# Gpio_RTC.net
KiCad netlist of a schematic drawn in Altium Designer
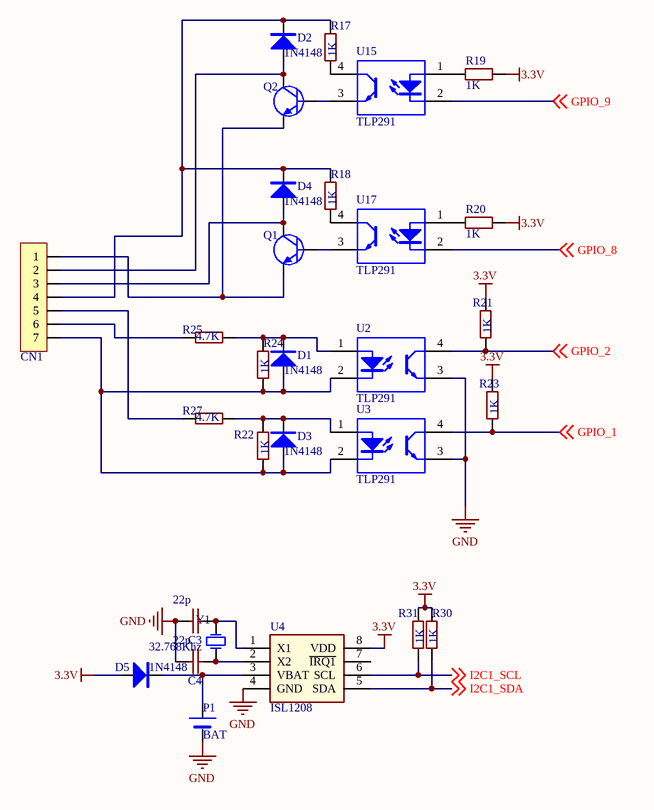
[diagram p0: Gpio_RTC.SchDoc]

(export (version "E")
  (design (tool "Eeschema 10.0.6"))
  (components
    (comp (ref "C3")
      (value "22p")
      (footprint "0805SMD_Cap")
      (description "贴片电容")
      (libsource (lib "ST_GND_Sch") (part "SMD_Cap"))
    )
    (comp (ref "C4")
      (value "22p")
      (footprint "0805SMD_Cap")
      (description "贴片电容")
      (libsource (lib "ST_GND_Sch") (part "SMD_Cap"))
    )
    (comp (ref "CN1")
      (value "CON7")
      (footprint "WJ15EDGRM-3.81-7P")
      (description "连接器")
      (libsource (lib "ST_GND_Sch") (part "CON7"))
    )
    (comp (ref "D1")
      (value "1N4148")
      (footprint "二极管SOD-123")
      (description "二极管")
      (libsource (lib "ST_GND_Sch") (part "DIODE"))
    )
    (comp (ref "D2")
      (value "1N4148")
      (footprint "二极管SOD-123")
      (description "二极管")
      (libsource (lib "ST_GND_Sch") (part "DIODE"))
    )
    (comp (ref "D3")
      (value "1N4148")
      (footprint "二极管SOD-123")
      (description "二极管")
      (libsource (lib "ST_GND_Sch") (part "DIODE"))
    )
    (comp (ref "D4")
      (value "1N4148")
      (footprint "二极管SOD-123")
      (description "二极管")
      (libsource (lib "ST_GND_Sch") (part "DIODE"))
    )
    (comp (ref "D5")
      (value "1N4148")
      (footprint "二极管SOD-123")
      (description "二极管")
      (libsource (lib "ST_GND_Sch") (part "DIODE"))
    )
    (comp (ref "P1") (value "BAT") (footprint "CR1220") (libsource (lib "ST_GND_Sch") (part "BAT")))
    (comp (ref "Q1")
      (value "1318")
      (footprint "SOT-23")
      (description "三极管")
      (fields (field (name "PUBLISHER") "Altium Limited"))
      (libsource (lib "ST_GND_Sch") (part "三极管"))
    )
    (comp (ref "Q2")
      (value "1318")
      (footprint "SOT-23")
      (description "三极管")
      (fields (field (name "PUBLISHER") "Altium Limited"))
      (libsource (lib "ST_GND_Sch") (part "三极管"))
    )
    (comp (ref "R17")
      (value "1K")
      (footprint "0805_SMD_R")
      (description "贴片电阻")
      (libsource (lib "ST_GND_Sch") (part "SMD_0805"))
    )
    (comp (ref "R18")
      (value "1K")
      (footprint "0805_SMD_R")
      (description "贴片电阻")
      (libsource (lib "ST_GND_Sch") (part "SMD_0805"))
    )
    (comp (ref "R19")
      (value "1K")
      (footprint "0805_SMD_R")
      (description "贴片电阻")
      (libsource (lib "") (part "SMD_0805_2"))
    )
    (comp (ref "R20")
      (value "1K")
      (footprint "0805_SMD_R")
      (description "贴片电阻")
      (libsource (lib "") (part "SMD_0805_2"))
    )
    (comp (ref "R21")
      (value "1K")
      (footprint "0805_SMD_R")
      (description "贴片电阻")
      (libsource (lib "ST_GND_Sch") (part "SMD_0805"))
    )
    (comp (ref "R22")
      (value "1K")
      (footprint "0805_SMD_R")
      (description "贴片电阻")
      (libsource (lib "ST_GND_Sch") (part "SMD_0805"))
    )
    (comp (ref "R23")
      (value "1K")
      (footprint "0805_SMD_R")
      (description "贴片电阻")
      (libsource (lib "ST_GND_Sch") (part "SMD_0805"))
    )
    (comp (ref "R24")
      (value "1K")
      (footprint "0805_SMD_R")
      (description "贴片电阻")
      (libsource (lib "ST_GND_Sch") (part "SMD_0805"))
    )
    (comp (ref "R25")
      (value "4.7K")
      (footprint "0805_SMD_R")
      (description "贴片电阻")
      (libsource (lib "") (part "SMD_0805_1"))
    )
    (comp (ref "R27")
      (value "4.7K")
      (footprint "0805_SMD_R")
      (description "贴片电阻")
      (libsource (lib "") (part "SMD_0805_1"))
    )
    (comp (ref "R30")
      (value "1K")
      (footprint "0805_SMD_R")
      (description "贴片电阻")
      (libsource (lib "") (part "SMD_0805_2"))
    )
    (comp (ref "R31")
      (value "1K")
      (footprint "0805_SMD_R")
      (description "贴片电阻")
      (libsource (lib "") (part "SMD_0805_2"))
    )
    (comp (ref "U2") (value "TLP291") (footprint "sop-4") (libsource (lib "ST_GND_Sch") (part "TLP291")))
    (comp (ref "U3") (value "TLP291") (footprint "sop-4") (libsource (lib "ST_GND_Sch") (part "TLP291")))
    (comp (ref "U4")
      (value "ISL1208")
      (footprint "运放SO8")
      (description "时钟芯片")
      (libsource (lib "ST_GND_Sch") (part "ISL1208"))
    )
    (comp (ref "U15") (value "TLP291") (footprint "sop-4") (libsource (lib "ST_GND_Sch") (part "TLP291")))
    (comp (ref "U17") (value "TLP291") (footprint "sop-4") (libsource (lib "ST_GND_Sch") (part "TLP291")))
    (comp (ref "Y1")
      (value "32.768Khz")
      (footprint "XTAL_0503_2Pin")
      (description "无源晶振贴装")
      (fields (field (name "PUBLISHER") "Altium Limited"))
      (libsource (lib "ST_GND_Sch") (part "XTAL"))
    )
  )
  (nets
    (net (code "1") (name "3.3V") (class "Default")
      (node (ref "D5") (pin "A") (pintype "passive"))
      (node (ref "R19") (pin "1") (pinfunction "1_1") (pintype "passive"))
      (node (ref "R20") (pin "1") (pinfunction "1_1") (pintype "passive"))
      (node (ref "R21") (pin "2") (pinfunction "2_2") (pintype "passive"))
      (node (ref "R23") (pin "2") (pinfunction "2_2") (pintype "passive"))
      (node (ref "R30") (pin "1") (pinfunction "1_1") (pintype "passive"))
      (node (ref "R31") (pin "1") (pinfunction "1_1") (pintype "passive"))
      (node (ref "U4") (pin "8") (pinfunction "VDD_8") (pintype "passive"))
    )
    (net (code "2") (name "GND") (class "Default")
      (node (ref "C3") (pin "1") (pintype "passive"))
      (node (ref "C4") (pin "1") (pintype "passive"))
      (node (ref "P1") (pin "2") (pinfunction "-_2") (pintype "passive"))
      (node (ref "U2") (pin "3") (pinfunction "3_3") (pintype "passive"))
      (node (ref "U3") (pin "3") (pinfunction "3_3") (pintype "passive"))
      (node (ref "U4") (pin "4") (pinfunction "GND_4") (pintype "passive"))
    )
    (net (code "3") (name "GPIO_1") (class "Default")
      (node (ref "R23") (pin "1") (pinfunction "1_1") (pintype "passive"))
      (node (ref "U3") (pin "4") (pinfunction "4_4") (pintype "passive"))
    )
    (net (code "4") (name "GPIO_2") (class "Default")
      (node (ref "R21") (pin "1") (pinfunction "1_1") (pintype "passive"))
      (node (ref "U2") (pin "4") (pinfunction "4_4") (pintype "passive"))
    )
    (net (code "5") (name "GPIO_8") (class "Default")
      (node (ref "U17") (pin "2") (pinfunction "2_2") (pintype "passive"))
    )
    (net (code "6") (name "GPIO_9") (class "Default")
      (node (ref "U15") (pin "2") (pinfunction "2_2") (pintype "passive"))
    )
    (net (code "7") (name "I2C1_SCL") (class "Default")
      (node (ref "R31") (pin "2") (pinfunction "2_2") (pintype "passive"))
      (node (ref "U4") (pin "6") (pinfunction "SCL_6") (pintype "passive"))
    )
    (net (code "8") (name "I2C1_SDA") (class "Default")
      (node (ref "R30") (pin "2") (pinfunction "2_2") (pintype "passive"))
      (node (ref "U4") (pin "5") (pinfunction "SDA_5") (pintype "passive"))
    )
    (net (code "9") (name "Net-(CN1-Pad4)") (class "Default")
      (node (ref "CN1") (pin "4") (pinfunction "4_4") (pintype "passive"))
      (node (ref "D2") (pin "K") (pintype "passive"))
      (node (ref "D4") (pin "K") (pintype "passive"))
      (node (ref "R17") (pin "2") (pinfunction "2_2") (pintype "passive"))
      (node (ref "R18") (pin "2") (pinfunction "2_2") (pintype "passive"))
    )
    (net (code "10") (name "Net-(CN1-Pad5)") (class "Default")
      (node (ref "CN1") (pin "5") (pinfunction "5_5") (pintype "passive"))
      (node (ref "R27") (pin "1") (pinfunction "1_1") (pintype "passive"))
    )
    (net (code "11") (name "Net-(CN1-Pad6)") (class "Default")
      (node (ref "CN1") (pin "6") (pinfunction "6_6") (pintype "passive"))
      (node (ref "R25") (pin "1") (pinfunction "1_1") (pintype "passive"))
    )
    (net (code "12") (name "Net-(CN1-Pad7)") (class "Default")
      (node (ref "CN1") (pin "7") (pinfunction "7_7") (pintype "passive"))
      (node (ref "D1") (pin "A") (pintype "passive"))
      (node (ref "D3") (pin "A") (pintype "passive"))
      (node (ref "R22") (pin "1") (pinfunction "1_1") (pintype "passive"))
      (node (ref "R24") (pin "1") (pinfunction "1_1") (pintype "passive"))
      (node (ref "U2") (pin "2") (pinfunction "2_2") (pintype "passive"))
      (node (ref "U3") (pin "2") (pinfunction "2_2") (pintype "passive"))
    )
    (net (code "13") (name "Net-(D1-PadK)") (class "Default")
      (node (ref "D1") (pin "K") (pintype "passive"))
      (node (ref "R24") (pin "2") (pinfunction "2_2") (pintype "passive"))
      (node (ref "R25") (pin "2") (pinfunction "2_2") (pintype "passive"))
      (node (ref "U2") (pin "1") (pinfunction "1_1") (pintype "passive"))
    )
    (net (code "14") (name "Net-(D3-PadK)") (class "Default")
      (node (ref "D3") (pin "K") (pintype "passive"))
      (node (ref "R22") (pin "2") (pinfunction "2_2") (pintype "passive"))
      (node (ref "R27") (pin "2") (pinfunction "2_2") (pintype "passive"))
      (node (ref "U3") (pin "1") (pinfunction "1_1") (pintype "passive"))
    )
    (net (code "15") (name "Net-(P1-+)") (class "Default")
      (node (ref "D5") (pin "K") (pintype "passive"))
      (node (ref "P1") (pin "1") (pinfunction "+_1") (pintype "passive"))
      (node (ref "U4") (pin "3") (pinfunction "VBAT_3") (pintype "passive"))
    )
    (net (code "16") (name "Net-(Q1-B)") (class "Default")
      (node (ref "Q1") (pin "1") (pinfunction "B_1") (pintype "passive"))
      (node (ref "U17") (pin "3") (pinfunction "3_3") (pintype "passive"))
    )
    (net (code "17") (name "Net-(Q1-C)") (class "Default")
      (node (ref "CN1") (pin "3") (pinfunction "3_3") (pintype "passive"))
      (node (ref "D4") (pin "A") (pintype "passive"))
      (node (ref "Q1") (pin "3") (pinfunction "C_3") (pintype "passive"))
    )
    (net (code "18") (name "Net-(Q1-E)") (class "Default")
      (node (ref "CN1") (pin "1") (pinfunction "1_1") (pintype "passive"))
      (node (ref "Q1") (pin "2") (pinfunction "E_2") (pintype "passive"))
      (node (ref "Q2") (pin "2") (pinfunction "E_2") (pintype "passive"))
    )
    (net (code "19") (name "Net-(Q2-B)") (class "Default")
      (node (ref "Q2") (pin "1") (pinfunction "B_1") (pintype "passive"))
      (node (ref "U15") (pin "3") (pinfunction "3_3") (pintype "passive"))
    )
    (net (code "20") (name "Net-(Q2-C)") (class "Default")
      (node (ref "CN1") (pin "2") (pinfunction "2_2") (pintype "passive"))
      (node (ref "D2") (pin "A") (pintype "passive"))
      (node (ref "Q2") (pin "3") (pinfunction "C_3") (pintype "passive"))
    )
    (net (code "21") (name "Net-(R17-Pad1)") (class "Default")
      (node (ref "R17") (pin "1") (pinfunction "1_1") (pintype "passive"))
      (node (ref "U15") (pin "4") (pinfunction "4_4") (pintype "passive"))
    )
    (net (code "22") (name "Net-(R18-Pad1)") (class "Default")
      (node (ref "R18") (pin "1") (pinfunction "1_1") (pintype "passive"))
      (node (ref "U17") (pin "4") (pinfunction "4_4") (pintype "passive"))
    )
    (net (code "23") (name "Net-(R19-Pad2)") (class "Default")
      (node (ref "R19") (pin "2") (pinfunction "2_2") (pintype "passive"))
      (node (ref "U15") (pin "1") (pinfunction "1_1") (pintype "passive"))
    )
    (net (code "24") (name "Net-(R20-Pad2)") (class "Default")
      (node (ref "R20") (pin "2") (pinfunction "2_2") (pintype "passive"))
      (node (ref "U17") (pin "1") (pinfunction "1_1") (pintype "passive"))
    )
    (net (code "25") (name "Net-(U4-X1)") (class "Default")
      (node (ref "C3") (pin "2") (pintype "passive"))
      (node (ref "U4") (pin "1") (pinfunction "X1_1") (pintype "passive"))
      (node (ref "Y1") (pin "2") (pinfunction "OSC2_2") (pintype "passive"))
    )
    (net (code "26") (name "Net-(U4-X2)") (class "Default")
      (node (ref "C4") (pin "2") (pintype "passive"))
      (node (ref "U4") (pin "2") (pinfunction "X2_2") (pintype "passive"))
      (node (ref "Y1") (pin "1") (pinfunction "OSC1_1") (pintype "passive"))
    )
    (net (code "27") (name "unconnected-(U4-~{IRQ1}-Pad7)") (class "Default")
      (node (ref "U4") (pin "7") (pinfunction "~{IRQ1}_7") (pintype "passive"))
    )
  )
)
